# 4_-CONNECTORS.net
KiCad netlist of a schematic drawn in Altium Designer
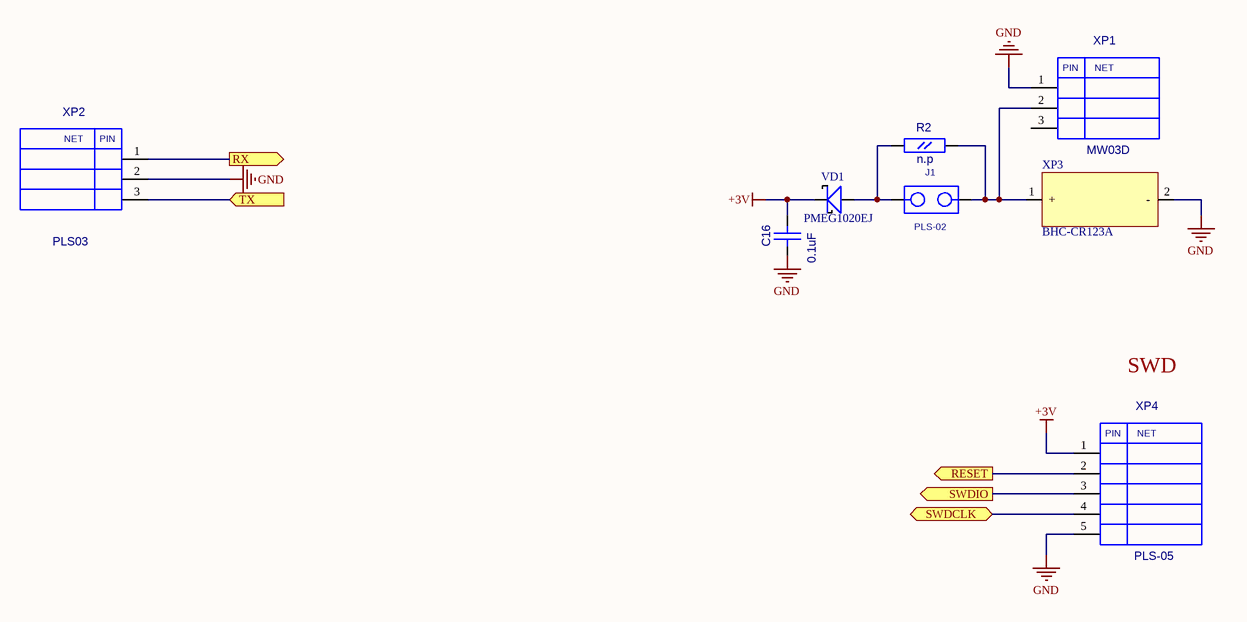
[diagram p0: [4]-CONNECTORS.SchDoc]

(export (version "E")
  (design (tool "Eeschema 10.0.6"))
  (components
    (comp (ref "C16")
      (value "0.1uF")
      (footprint "CC0603")
      (description "CC0603")
      (libsource (lib "fizik_lib") (part "CC0603"))
    )
    (comp (ref "J1") (value "PLS-02") (footprint "PLS-02") (libsource (lib "fizik_lib") (part "PLS-02")))
    (comp (ref "R2")
      (value "n.p")
      (footprint "RC0603")
      (description "RC0603")
      (libsource (lib "fizik_lib") (part "RC0603"))
    )
    (comp (ref "VD1")
      (value "PMEG1020EJ")
      (footprint "SOD323")
      (libsource (lib "fizik_lib") (part "PMEG2010"))
    )
    (comp (ref "XP1") (value "MW03D") (footprint "MW03D") (libsource (lib "gprs_modem_2") (part "MW03D")))
    (comp (ref "XP2") (value "PLS03") (footprint "PLS-03") (libsource (lib "fizik_lib") (part "PLS03")))
    (comp (ref "XP3")
      (value "BHC-CR123A")
      (footprint "CR123_HOLDER")
      (description "Holder for CR123 battery")
      (libsource (lib "fizik_lib") (part "BHC-CR123A"))
    )
    (comp (ref "XP4") (value "PLS-05") (footprint "PLS-05") (libsource (lib "gprs_modem_2") (part "PLS-05")))
  )
  (nets
    (net (code "1") (name "+3V") (class "Default")
      (node (ref "C16") (pin "2") (pinfunction "B_2") (pintype "passive"))
      (node (ref "VD1") (pin "2") (pinfunction "K_2") (pintype "passive"))
      (node (ref "XP4") (pin "1") (pinfunction "1_1") (pintype "passive"))
    )
    (net (code "2") (name "/RESET") (class "Default")
      (node (ref "XP4") (pin "2") (pinfunction "2_2") (pintype "passive"))
    )
    (net (code "3") (name "/RX") (class "Default")
      (node (ref "XP2") (pin "1") (pinfunction "1_1") (pintype "passive"))
    )
    (net (code "4") (name "/SWDCLK") (class "Default")
      (node (ref "XP4") (pin "4") (pinfunction "4_4") (pintype "passive"))
    )
    (net (code "5") (name "/SWDIO") (class "Default")
      (node (ref "XP4") (pin "3") (pinfunction "3_3") (pintype "passive"))
    )
    (net (code "6") (name "/TX") (class "Default")
      (node (ref "XP2") (pin "3") (pinfunction "3_3") (pintype "passive"))
    )
    (net (code "7") (name "GND") (class "Default")
      (node (ref "C16") (pin "1") (pinfunction "A_1") (pintype "passive"))
      (node (ref "XP1") (pin "1") (pinfunction "1_1") (pintype "passive"))
      (node (ref "XP2") (pin "2") (pinfunction "2_2") (pintype "passive"))
      (node (ref "XP3") (pin "2") (pinfunction "-_2") (pintype "passive"))
      (node (ref "XP4") (pin "5") (pinfunction "5_5") (pintype "passive"))
    )
    (net (code "8") (name "Net-(R2-A)") (class "Default")
      (node (ref "J1") (pin "1") (pintype "passive"))
      (node (ref "R2") (pin "1") (pinfunction "A_1") (pintype "passive"))
      (node (ref "VD1") (pin "1") (pinfunction "A_1") (pintype "passive"))
    )
    (net (code "9") (name "Net-(R2-B)") (class "Default")
      (node (ref "J1") (pin "2") (pintype "passive"))
      (node (ref "R2") (pin "2") (pinfunction "B_2") (pintype "passive"))
      (node (ref "XP1") (pin "2") (pinfunction "2_2") (pintype "passive"))
      (node (ref "XP3") (pin "1") (pinfunction "+_1") (pintype "passive"))
    )
    (net (code "10") (name "unconnected-(XP1-Pad3)") (class "Default")
      (node (ref "XP1") (pin "3") (pinfunction "3_3") (pintype "passive"))
    )
  )
)
